# COMS0004_4_ModemRXMux.net
KiCad netlist of a schematic drawn in Altium Designer
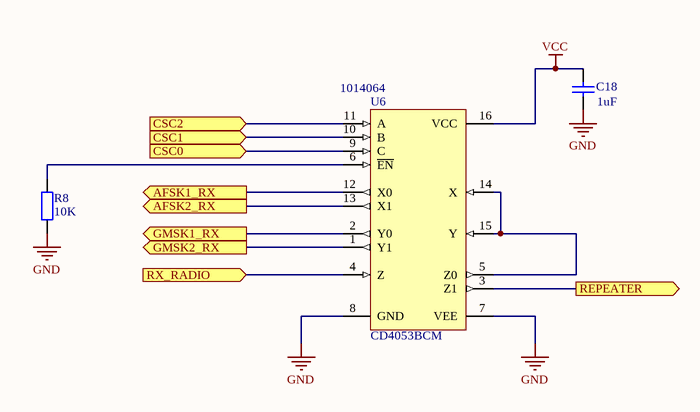
[diagram p0: COMS0004_4_ModemRXMux.SchDoc]

(export (version "E")
  (design (tool "Eeschema 10.0.6"))
  (components
    (comp (ref "C18")
      (value "1uF")
      (footprint "0805")
      (description "Capacitor")
      (fields (field (name "Comment") "C1210") (field (name "PUBLISHER") "Altium Limited"))
      (libsource (lib "Miscellaneous Devices") (part "Cap"))
    )
    (comp (ref "R8")
      (value "10K")
      (footprint "RESC2012N")
      (description "Resistor")
      (fields (field (name "Comment") "Res1") (field (name "PUBLISHER") "Altium Limited"))
      (libsource (lib "Miscellaneous Devices") (part "Res2"))
    )
    (comp (ref "U6")
      (value "CD4053BCM")
      (footprint "M16A_M")
      (description "Triple 2-Channnel Analog Multiplexer/Demutiplexer")
      (fields (field (name "SUPPLIER PART NUMBER 1") "1014064") (field (name "PUBLISHER") "Altium Limited"))
      (libsource (lib "FSC Logic Multiplexer") (part "CD4053BCM"))
    )
  )
  (nets
    (net (code "1") (name "/AFSK1_RX") (class "Default")
      (node (ref "U6") (pin "12") (pinfunction "X0_12") (pintype "output"))
    )
    (net (code "2") (name "/AFSK2_RX") (class "Default")
      (node (ref "U6") (pin "13") (pinfunction "X1_13") (pintype "output"))
    )
    (net (code "3") (name "/CSC0") (class "Default")
      (node (ref "U6") (pin "9") (pinfunction "C_9") (pintype "input"))
    )
    (net (code "4") (name "/CSC1") (class "Default")
      (node (ref "U6") (pin "10") (pinfunction "B_10") (pintype "input"))
    )
    (net (code "5") (name "/CSC2") (class "Default")
      (node (ref "U6") (pin "11") (pinfunction "A_11") (pintype "input"))
    )
    (net (code "6") (name "/GMSK1_RX") (class "Default")
      (node (ref "U6") (pin "2") (pinfunction "Y0_2") (pintype "output"))
    )
    (net (code "7") (name "/GMSK2_RX") (class "Default")
      (node (ref "U6") (pin "1") (pinfunction "Y1_1") (pintype "output"))
    )
    (net (code "8") (name "/REPEATER") (class "Default")
      (node (ref "U6") (pin "3") (pinfunction "Z1_3") (pintype "output"))
    )
    (net (code "9") (name "/RX_RADIO") (class "Default")
      (node (ref "U6") (pin "4") (pinfunction "Z_4") (pintype "input"))
    )
    (net (code "10") (name "GND") (class "Default")
      (node (ref "C18") (pin "1") (pinfunction "1_1") (pintype "passive"))
      (node (ref "R8") (pin "1") (pinfunction "1_1") (pintype "passive"))
      (node (ref "U6") (pin "7") (pinfunction "VEE_7") (pintype "power_in"))
      (node (ref "U6") (pin "8") (pinfunction "GND_8") (pintype "power_in"))
    )
    (net (code "11") (name "Net-(U6-X)") (class "Default")
      (node (ref "U6") (pin "14") (pinfunction "X_14") (pintype "input"))
      (node (ref "U6") (pin "15") (pinfunction "Y_15") (pintype "input"))
      (node (ref "U6") (pin "5") (pinfunction "Z0_5") (pintype "output"))
    )
    (net (code "12") (name "Net-(U6-~{EN})") (class "Default")
      (node (ref "R8") (pin "2") (pinfunction "2_2") (pintype "passive"))
      (node (ref "U6") (pin "6") (pinfunction "~{EN}_6") (pintype "input"))
    )
    (net (code "13") (name "VCC") (class "Default")
      (node (ref "C18") (pin "2") (pinfunction "2_2") (pintype "passive"))
      (node (ref "U6") (pin "16") (pinfunction "VCC_16") (pintype "power_in"))
    )
  )
)
